# aLCD.net
KiCad netlist of a schematic drawn in Altium Designer
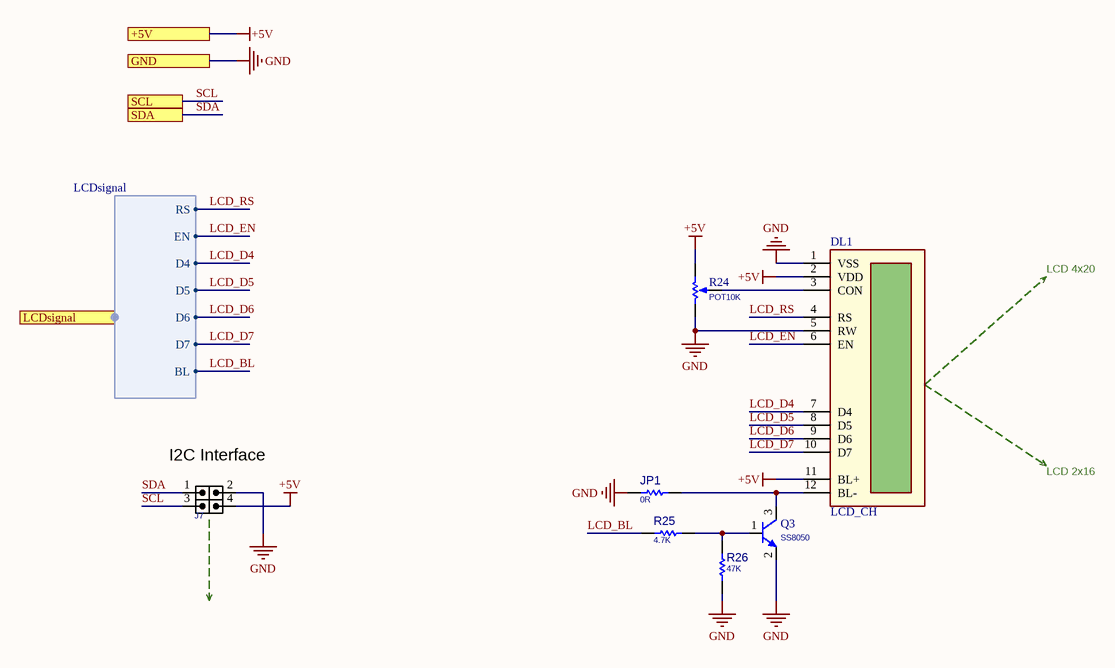
[diagram p0: aLCD.SchDoc]

(export (version "E")
  (design (tool "Eeschema 10.0.6"))
  (components
    (comp (ref "DL1")
      (value "LCD_CH")
      (footprint "LCD_CH")
      (description "alphanumeric lcd  2x16")
      (libsource (lib "Mehrdad") (part "LCD_CH"))
    )
    (comp (ref "J7")
      (value "HDRM_2X2")
      (footprint "HDR_M_2X2")
      (description "CONN, HEADER, Male, pitch: 2.54mm, 4POS")
      (fields (field (name "MANF_P#") "MANF_PART#") (field (name "MANF") "MANF"))
      (libsource (lib "conn_header_2.54_st") (part "HDR_M_2X2"))
    )
    (comp (ref "JP1")
      (value "0R")
      (footprint "R0805")
      (description "RESISTOR, SMD")
      (libsource (lib "passive_smd") (part "RES_SMD_0805"))
    )
    (comp (ref "Q3")
      (value "SS8050")
      (footprint "SOT23_3")
      (description "BJT, NPN, 25v, 1.5A, SMD, SOT23")
      (fields (field (name "MANF") "GALAXY"))
      (libsource (lib "transistor_bjt") (part "NPN_SS8050_SOT23"))
    )
    (comp (ref "R24")
      (value "POT10K")
      (footprint "POT_7X5")
      (description "RESISTOR, THD, Potentiometer")
      (libsource (lib "resistor_pot_trimmer") (part "RES_THD_POT_7X5"))
    )
    (comp (ref "R25")
      (value "4.7K")
      (footprint "R0805")
      (description "RESISTOR, SMD")
      (libsource (lib "passive_smd") (part "RES_SMD_0805"))
    )
    (comp (ref "R26")
      (value "47K")
      (footprint "R0805")
      (description "RESISTOR, SMD")
      (libsource (lib "passive_smd") (part "RES_SMD_0805"))
    )
  )
  (nets
    (net (code "2") (name "+5V") (class "Default")
      (node (ref "DL1") (pin "11") (pinfunction "BL+_11") (pintype "passive"))
      (node (ref "DL1") (pin "2") (pinfunction "VDD_2") (pintype "passive"))
      (node (ref "J7") (pin "4") (pinfunction "4_4") (pintype "passive"))
      (node (ref "R24") (pin "1") (pinfunction "TOP_1") (pintype "passive"))
    )
    (net (code "3") (name "/LCD_BL") (class "Default")
      (node (ref "R25") (pin "2") (pinfunction "2_2") (pintype "passive"))
    )
    (net (code "4") (name "/LCD_D4") (class "Default")
      (node (ref "DL1") (pin "7") (pinfunction "D4_7") (pintype "passive"))
    )
    (net (code "5") (name "/LCD_D5") (class "Default")
      (node (ref "DL1") (pin "8") (pinfunction "D5_8") (pintype "passive"))
    )
    (net (code "6") (name "/LCD_D6") (class "Default")
      (node (ref "DL1") (pin "9") (pinfunction "D6_9") (pintype "passive"))
    )
    (net (code "7") (name "/LCD_D7") (class "Default")
      (node (ref "DL1") (pin "10") (pinfunction "D7_10") (pintype "passive"))
    )
    (net (code "8") (name "/LCD_EN") (class "Default")
      (node (ref "DL1") (pin "6") (pinfunction "EN_6") (pintype "passive"))
    )
    (net (code "9") (name "/LCD_RS") (class "Default")
      (node (ref "DL1") (pin "4") (pinfunction "RS_4") (pintype "passive"))
    )
    (net (code "10") (name "/SCL") (class "Default")
      (node (ref "J7") (pin "3") (pinfunction "3_3") (pintype "passive"))
    )
    (net (code "11") (name "/SDA") (class "Default")
      (node (ref "J7") (pin "1") (pinfunction "1_1") (pintype "passive"))
    )
    (net (code "13") (name "GND") (class "Default")
      (node (ref "DL1") (pin "1") (pinfunction "VSS_1") (pintype "passive"))
      (node (ref "DL1") (pin "5") (pinfunction "RW_5") (pintype "passive"))
      (node (ref "J7") (pin "2") (pinfunction "2_2") (pintype "passive"))
      (node (ref "JP1") (pin "2") (pinfunction "2_2") (pintype "passive"))
      (node (ref "Q3") (pin "2") (pinfunction "E_2") (pintype "passive"))
      (node (ref "R24") (pin "3") (pinfunction "BOT_3") (pintype "passive"))
      (node (ref "R26") (pin "2") (pinfunction "2_2") (pintype "passive"))
    )
    (net (code "14") (name "Net-(DL1-BL-)") (class "Default")
      (node (ref "DL1") (pin "12") (pinfunction "BL-_12") (pintype "passive"))
      (node (ref "JP1") (pin "1") (pinfunction "1_1") (pintype "passive"))
      (node (ref "Q3") (pin "3") (pinfunction "C_3") (pintype "passive"))
    )
    (net (code "15") (name "Net-(DL1-CON)") (class "Default")
      (node (ref "DL1") (pin "3") (pinfunction "CON_3") (pintype "passive"))
      (node (ref "R24") (pin "2") (pinfunction "TAP_2") (pintype "passive"))
    )
    (net (code "16") (name "Net-(Q3-B)") (class "Default")
      (node (ref "Q3") (pin "1") (pinfunction "B_1") (pintype "passive"))
      (node (ref "R25") (pin "1") (pinfunction "1_1") (pintype "passive"))
      (node (ref "R26") (pin "1") (pinfunction "1_1") (pintype "passive"))
    )
  )
)
